# S2EC13.net
KiCad netlist of a schematic drawn in EAGLE
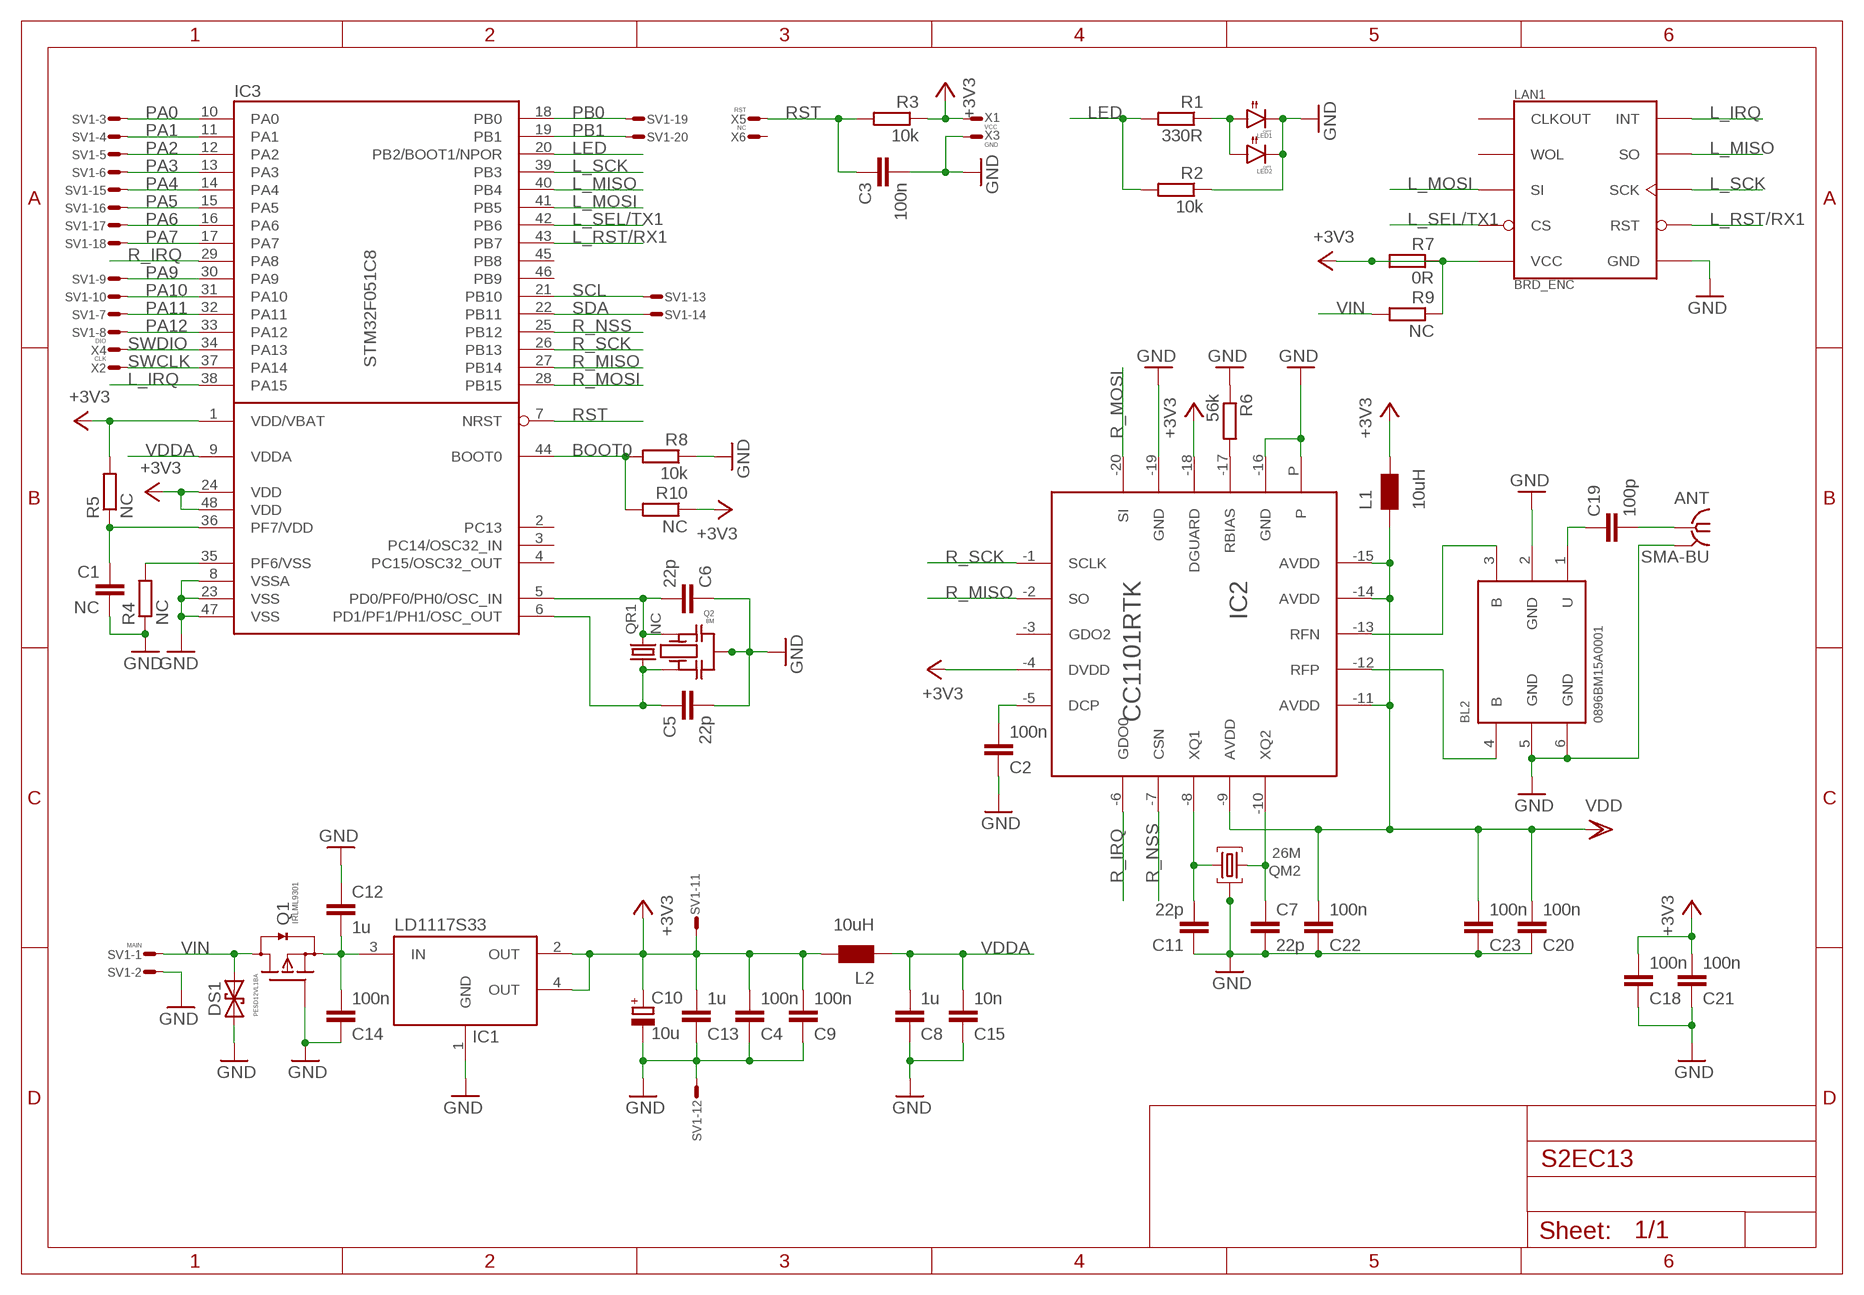
[diagram p0: schematic, sheet 1]

(export (version "E")
  (design (tool "Eeschema 10.0.6"))
  (components
    (comp (ref "ANT")
      (value "SMA-BU")
      (footprint "eagle-import:BU-SMA-V")
      (libsource (lib "eagle-import") (part "SMA-BU"))
    )
    (comp (ref "BL2")
      (value "0896BM15A0001")
      (footprint "eagle-import:BL")
      (libsource (lib "eagle-import") (part "BL"))
    )
    (comp (ref "C1")
      (value "NC")
      (footprint "eagle-import:0603")
      (libsource (lib "eagle-import") (part "C0603"))
    )
    (comp (ref "C2")
      (value "100n")
      (footprint "eagle-import:0603")
      (libsource (lib "eagle-import") (part "C0603"))
    )
    (comp (ref "C3")
      (value "100n")
      (footprint "eagle-import:0603")
      (libsource (lib "eagle-import") (part "C0603"))
    )
    (comp (ref "C4")
      (value "100n")
      (footprint "eagle-import:0603")
      (libsource (lib "eagle-import") (part "C0603"))
    )
    (comp (ref "C5")
      (value "22p")
      (footprint "eagle-import:0603")
      (libsource (lib "eagle-import") (part "C0603"))
    )
    (comp (ref "C6")
      (value "22p")
      (footprint "eagle-import:0603")
      (libsource (lib "eagle-import") (part "C0603"))
    )
    (comp (ref "C7")
      (value "22p")
      (footprint "eagle-import:0603")
      (libsource (lib "eagle-import") (part "C0603"))
    )
    (comp (ref "C8")
      (value "1u")
      (footprint "eagle-import:0603")
      (libsource (lib "eagle-import") (part "C0603"))
    )
    (comp (ref "C9")
      (value "100n")
      (footprint "eagle-import:0603")
      (libsource (lib "eagle-import") (part "C0603"))
    )
    (comp (ref "C10")
      (value "10u")
      (footprint "eagle-import:SMC_A")
      (libsource (lib "eagle-import") (part "C_POLSMCA"))
    )
    (comp (ref "C11")
      (value "22p")
      (footprint "eagle-import:0603")
      (libsource (lib "eagle-import") (part "C0603"))
    )
    (comp (ref "C12")
      (value "1u")
      (footprint "eagle-import:0603")
      (libsource (lib "eagle-import") (part "C0603"))
    )
    (comp (ref "C13")
      (value "1u")
      (footprint "eagle-import:0603")
      (libsource (lib "eagle-import") (part "C0603"))
    )
    (comp (ref "C14")
      (value "100n")
      (footprint "eagle-import:0603")
      (libsource (lib "eagle-import") (part "C0603"))
    )
    (comp (ref "C15")
      (value "10n")
      (footprint "eagle-import:0603")
      (libsource (lib "eagle-import") (part "C0603"))
    )
    (comp (ref "C18")
      (value "100n")
      (footprint "eagle-import:0603")
      (libsource (lib "eagle-import") (part "C0603"))
    )
    (comp (ref "C19")
      (value "100p")
      (footprint "eagle-import:0603")
      (libsource (lib "eagle-import") (part "C0603"))
    )
    (comp (ref "C20")
      (value "100n")
      (footprint "eagle-import:0603")
      (libsource (lib "eagle-import") (part "C0603"))
    )
    (comp (ref "C21")
      (value "100n")
      (footprint "eagle-import:0603")
      (libsource (lib "eagle-import") (part "C0603"))
    )
    (comp (ref "C22")
      (value "100n")
      (footprint "eagle-import:0603")
      (libsource (lib "eagle-import") (part "C0603"))
    )
    (comp (ref "C23")
      (value "100n")
      (footprint "eagle-import:0603")
      (libsource (lib "eagle-import") (part "C0603"))
    )
    (comp (ref "DS1")
      (value "PESD12VL1BA")
      (footprint "eagle-import:SOD323")
      (libsource (lib "eagle-import") (part "TVS-U323"))
    )
    (comp (ref "IC1")
      (value "LD1117S33")
      (footprint "eagle-import:SOT223")
      (libsource (lib "eagle-import") (part "LDO_4P"))
    )
    (comp (ref "IC2")
      (value "CC1101RTK")
      (footprint "eagle-import:VQFN20")
      (libsource (lib "eagle-import") (part "CC110LV"))
    )
    (comp (ref "IC3")
      (value "STM32F051C8")
      (footprint "eagle-import:LQFP48")
      (libsource (lib "eagle-import") (part "STM32_LQFP48"))
    )
    (comp (ref "L1")
      (value "10uH")
      (footprint "eagle-import:0603")
      (libsource (lib "eagle-import") (part "L0603"))
    )
    (comp (ref "L2")
      (value "10uH")
      (footprint "eagle-import:0603")
      (libsource (lib "eagle-import") (part "L0603"))
    )
    (comp (ref "LAN1")
      (value "BRD_ENC")
      (footprint "eagle-import:BRD_ENC")
      (libsource (lib "eagle-import") (part "BRD_ENC"))
    )
    (comp (ref "LED1")
      (value "OPT")
      (footprint "eagle-import:T1-3_4")
      (libsource (lib "eagle-import") (part "LEDT134"))
    )
    (comp (ref "LED2")
      (value "OPT")
      (footprint "eagle-import:1206")
      (libsource (lib "eagle-import") (part "LED1206"))
    )
    (comp (ref "Q1")
      (value "IRLML9301")
      (footprint "eagle-import:SOT23")
      (libsource (lib "eagle-import") (part "FET-PDSOT23"))
    )
    (comp (ref "Q2")
      (value "8M")
      (footprint "eagle-import:CSTCE")
      (libsource (lib "eagle-import") (part "QRCE"))
    )
    (comp (ref "QM2")
      (value "26M")
      (footprint "eagle-import:SMD_4P_3.2X2.5")
      (libsource (lib "eagle-import") (part "QM3.2X2.5"))
    )
    (comp (ref "QR1")
      (value "NC")
      (footprint "eagle-import:ABS07")
      (libsource (lib "eagle-import") (part "QABS07"))
    )
    (comp (ref "R1")
      (value "330R")
      (footprint "eagle-import:0603")
      (libsource (lib "eagle-import") (part "R0603"))
    )
    (comp (ref "R2")
      (value "10k")
      (footprint "eagle-import:0603")
      (libsource (lib "eagle-import") (part "R0603"))
    )
    (comp (ref "R3")
      (value "10k")
      (footprint "eagle-import:0603")
      (libsource (lib "eagle-import") (part "R0603"))
    )
    (comp (ref "R4")
      (value "NC")
      (footprint "eagle-import:0603")
      (libsource (lib "eagle-import") (part "R0603"))
    )
    (comp (ref "R5")
      (value "NC")
      (footprint "eagle-import:0603")
      (libsource (lib "eagle-import") (part "R0603"))
    )
    (comp (ref "R6")
      (value "56k")
      (footprint "eagle-import:0603")
      (libsource (lib "eagle-import") (part "R0603"))
    )
    (comp (ref "R7")
      (value "0R")
      (footprint "eagle-import:0603")
      (libsource (lib "eagle-import") (part "R0603"))
    )
    (comp (ref "R8")
      (value "10k")
      (footprint "eagle-import:0603")
      (libsource (lib "eagle-import") (part "R0603"))
    )
    (comp (ref "R9")
      (value "NC")
      (footprint "eagle-import:0603")
      (libsource (lib "eagle-import") (part "R0603"))
    )
    (comp (ref "R10")
      (value "NC")
      (footprint "eagle-import:0603")
      (libsource (lib "eagle-import") (part "R0603"))
    )
    (comp (ref "SV1")
      (value "MAIN")
      (footprint "eagle-import:ML20LS")
      (libsource (lib "eagle-import") (part "ML20?ELS"))
    )
    (comp (ref "X1")
      (value "VCC")
      (footprint "eagle-import:T1.6_0.9")
      (libsource (lib "eagle-import") (part "WIREPADT1.6/0.9"))
    )
    (comp (ref "X2")
      (value "CLK")
      (footprint "eagle-import:T1.6_0.9")
      (libsource (lib "eagle-import") (part "WIREPADT1.6/0.9"))
    )
    (comp (ref "X3")
      (value "GND")
      (footprint "eagle-import:T1.6_0.9")
      (libsource (lib "eagle-import") (part "WIREPADT1.6/0.9"))
    )
    (comp (ref "X4")
      (value "DIO")
      (footprint "eagle-import:T1.6_0.9")
      (libsource (lib "eagle-import") (part "WIREPADT1.6/0.9"))
    )
    (comp (ref "X5")
      (value "RST")
      (footprint "eagle-import:T1.6_0.9")
      (libsource (lib "eagle-import") (part "WIREPADT1.6/0.9"))
    )
    (comp (ref "X6")
      (value "NC")
      (footprint "eagle-import:T1.6_0.9")
      (libsource (lib "eagle-import") (part "WIREPADT1.6/0.9"))
    )
  )
  (nets
    (net (code "1") (name "+3V3") (class "Default")
      (node (ref "C10") (pin "+") (pinfunction "+_+") (pintype "passive"))
      (node (ref "C13") (pin "2") (pinfunction "2_2") (pintype "passive"))
      (node (ref "C18") (pin "2") (pinfunction "2_2") (pintype "passive"))
      (node (ref "C21") (pin "2") (pinfunction "2_2") (pintype "passive"))
      (node (ref "C4") (pin "2") (pinfunction "2_2") (pintype "passive"))
      (node (ref "C9") (pin "2") (pinfunction "2_2") (pintype "passive"))
      (node (ref "IC1") (pin "2") (pinfunction "OUT_2") (pintype "bidirectional"))
      (node (ref "IC1") (pin "4") (pinfunction "OUT_4") (pintype "bidirectional"))
      (node (ref "IC2") (pin "-18") (pinfunction "DGUARD_-18") (pintype "bidirectional"))
      (node (ref "IC2") (pin "-4") (pinfunction "DVDD_-4") (pintype "bidirectional"))
      (node (ref "IC3") (pin "1") (pinfunction "VDD/VBAT_1") (pintype "bidirectional"))
      (node (ref "IC3") (pin "24") (pinfunction "VDD_24") (pintype "bidirectional"))
      (node (ref "IC3") (pin "48") (pinfunction "VDD_48") (pintype "bidirectional"))
      (node (ref "L1") (pin "2") (pinfunction "2_2") (pintype "passive"))
      (node (ref "L2") (pin "2") (pinfunction "2_2") (pintype "passive"))
      (node (ref "LAN1") (pin "P$9") (pinfunction "VCC_P$9") (pintype "bidirectional"))
      (node (ref "R10") (pin "1") (pinfunction "1_1") (pintype "passive"))
      (node (ref "R3") (pin "1") (pinfunction "1_1") (pintype "passive"))
      (node (ref "R5") (pin "2") (pinfunction "2_2") (pintype "passive"))
      (node (ref "R7") (pin "1") (pinfunction "1_1") (pintype "passive"))
      (node (ref "R7") (pin "2") (pinfunction "2_2") (pintype "passive"))
      (node (ref "R9") (pin "1") (pinfunction "1_1") (pintype "passive"))
      (node (ref "SV1") (pin "P$11") (pinfunction "S_P$11") (pintype "passive"))
      (node (ref "X1") (pin "1") (pinfunction "S_1") (pintype "passive"))
    )
    (net (code "2") (name "/BOOT0") (class "Default")
      (node (ref "IC3") (pin "44") (pinfunction "BOOT0_44") (pintype "bidirectional"))
      (node (ref "R10") (pin "2") (pinfunction "2_2") (pintype "passive"))
      (node (ref "R8") (pin "2") (pinfunction "2_2") (pintype "passive"))
    )
    (net (code "3") (name "/LED") (class "Default")
      (node (ref "IC3") (pin "20") (pinfunction "PB2/BOOT1/NPOR_20") (pintype "bidirectional"))
      (node (ref "R1") (pin "2") (pinfunction "2_2") (pintype "passive"))
      (node (ref "R2") (pin "2") (pinfunction "2_2") (pintype "passive"))
    )
    (net (code "4") (name "/L_IRQ") (class "Default")
      (node (ref "IC3") (pin "38") (pinfunction "PA15_38") (pintype "bidirectional"))
      (node (ref "LAN1") (pin "P$2") (pinfunction "INT_P$2") (pintype "open_collector"))
    )
    (net (code "5") (name "/L_MISO") (class "Default")
      (node (ref "IC3") (pin "40") (pinfunction "PB4_40") (pintype "bidirectional"))
      (node (ref "LAN1") (pin "P$4") (pinfunction "SO_P$4") (pintype "output"))
    )
    (net (code "6") (name "/L_MOSI") (class "Default")
      (node (ref "IC3") (pin "41") (pinfunction "PB5_41") (pintype "bidirectional"))
      (node (ref "LAN1") (pin "P$5") (pinfunction "SI_P$5") (pintype "input"))
    )
    (net (code "7") (name "/L_RST{slash}RX1") (class "Default")
      (node (ref "IC3") (pin "43") (pinfunction "PB7_43") (pintype "bidirectional"))
      (node (ref "LAN1") (pin "P$8") (pinfunction "RST_P$8") (pintype "bidirectional"))
    )
    (net (code "8") (name "/L_SCK") (class "Default")
      (node (ref "IC3") (pin "39") (pinfunction "PB3_39") (pintype "bidirectional"))
      (node (ref "LAN1") (pin "P$6") (pinfunction "SCK_P$6") (pintype "input"))
    )
    (net (code "9") (name "/L_SEL{slash}TX1") (class "Default")
      (node (ref "IC3") (pin "42") (pinfunction "PB6_42") (pintype "bidirectional"))
      (node (ref "LAN1") (pin "P$7") (pinfunction "CS_P$7") (pintype "input"))
    )
    (net (code "10") (name "/PA0") (class "Default")
      (node (ref "IC3") (pin "10") (pinfunction "PA0_10") (pintype "bidirectional"))
      (node (ref "SV1") (pin "P$3") (pinfunction "S_P$3") (pintype "passive"))
    )
    (net (code "11") (name "/PA1") (class "Default")
      (node (ref "IC3") (pin "11") (pinfunction "PA1_11") (pintype "bidirectional"))
      (node (ref "SV1") (pin "P$4") (pinfunction "S_P$4") (pintype "passive"))
    )
    (net (code "12") (name "/PA2") (class "Default")
      (node (ref "IC3") (pin "12") (pinfunction "PA2_12") (pintype "bidirectional"))
      (node (ref "SV1") (pin "P$5") (pinfunction "S_P$5") (pintype "passive"))
    )
    (net (code "13") (name "/PA3") (class "Default")
      (node (ref "IC3") (pin "13") (pinfunction "PA3_13") (pintype "bidirectional"))
      (node (ref "SV1") (pin "P$6") (pinfunction "S_P$6") (pintype "passive"))
    )
    (net (code "14") (name "/PA4") (class "Default")
      (node (ref "IC3") (pin "14") (pinfunction "PA4_14") (pintype "bidirectional"))
      (node (ref "SV1") (pin "P$15") (pinfunction "S_P$15") (pintype "passive"))
    )
    (net (code "15") (name "/PA5") (class "Default")
      (node (ref "IC3") (pin "15") (pinfunction "PA5_15") (pintype "bidirectional"))
      (node (ref "SV1") (pin "P$16") (pinfunction "S_P$16") (pintype "passive"))
    )
    (net (code "16") (name "/PA6") (class "Default")
      (node (ref "IC3") (pin "16") (pinfunction "PA6_16") (pintype "bidirectional"))
      (node (ref "SV1") (pin "P$17") (pinfunction "S_P$17") (pintype "passive"))
    )
    (net (code "17") (name "/PA7") (class "Default")
      (node (ref "IC3") (pin "17") (pinfunction "PA7_17") (pintype "bidirectional"))
      (node (ref "SV1") (pin "P$18") (pinfunction "S_P$18") (pintype "passive"))
    )
    (net (code "18") (name "/PA9") (class "Default")
      (node (ref "IC3") (pin "30") (pinfunction "PA9_30") (pintype "bidirectional"))
      (node (ref "SV1") (pin "P$9") (pinfunction "S_P$9") (pintype "passive"))
    )
    (net (code "19") (name "/PA10") (class "Default")
      (node (ref "IC3") (pin "31") (pinfunction "PA10_31") (pintype "bidirectional"))
      (node (ref "SV1") (pin "P$10") (pinfunction "S_P$10") (pintype "passive"))
    )
    (net (code "20") (name "/PA11") (class "Default")
      (node (ref "IC3") (pin "32") (pinfunction "PA11_32") (pintype "bidirectional"))
      (node (ref "SV1") (pin "P$7") (pinfunction "S_P$7") (pintype "passive"))
    )
    (net (code "21") (name "/PA12") (class "Default")
      (node (ref "IC3") (pin "33") (pinfunction "PA12_33") (pintype "bidirectional"))
      (node (ref "SV1") (pin "P$8") (pinfunction "S_P$8") (pintype "passive"))
    )
    (net (code "22") (name "/PB0") (class "Default")
      (node (ref "IC3") (pin "18") (pinfunction "PB0_18") (pintype "bidirectional"))
      (node (ref "SV1") (pin "P$19") (pinfunction "S_P$19") (pintype "passive"))
    )
    (net (code "23") (name "/PB1") (class "Default")
      (node (ref "IC3") (pin "19") (pinfunction "PB1_19") (pintype "bidirectional"))
      (node (ref "SV1") (pin "P$20") (pinfunction "S_P$20") (pintype "passive"))
    )
    (net (code "24") (name "/RST") (class "Default")
      (node (ref "C3") (pin "1") (pinfunction "1_1") (pintype "passive"))
      (node (ref "IC3") (pin "7") (pinfunction "NRST_7") (pintype "bidirectional"))
      (node (ref "R3") (pin "2") (pinfunction "2_2") (pintype "passive"))
      (node (ref "X5") (pin "1") (pinfunction "S_1") (pintype "passive"))
    )
    (net (code "25") (name "/R_IRQ") (class "Default")
      (node (ref "IC2") (pin "-6") (pinfunction "GDO0_-6") (pintype "bidirectional"))
      (node (ref "IC3") (pin "29") (pinfunction "PA8_29") (pintype "bidirectional"))
    )
    (net (code "26") (name "/R_MISO") (class "Default")
      (node (ref "IC2") (pin "-2") (pinfunction "SO_-2") (pintype "output"))
      (node (ref "IC3") (pin "27") (pinfunction "PB14_27") (pintype "bidirectional"))
    )
    (net (code "27") (name "/R_MOSI") (class "Default")
      (node (ref "IC2") (pin "-20") (pinfunction "SI_-20") (pintype "input"))
      (node (ref "IC3") (pin "28") (pinfunction "PB15_28") (pintype "bidirectional"))
    )
    (net (code "28") (name "/R_NSS") (class "Default")
      (node (ref "IC2") (pin "-7") (pinfunction "CSN_-7") (pintype "input"))
      (node (ref "IC3") (pin "25") (pinfunction "PB12_25") (pintype "bidirectional"))
    )
    (net (code "29") (name "/R_SCK") (class "Default")
      (node (ref "IC2") (pin "-1") (pinfunction "SCLK_-1") (pintype "input"))
      (node (ref "IC3") (pin "26") (pinfunction "PB13_26") (pintype "bidirectional"))
    )
    (net (code "30") (name "/SCL") (class "Default")
      (node (ref "IC3") (pin "21") (pinfunction "PB10_21") (pintype "bidirectional"))
      (node (ref "SV1") (pin "P$13") (pinfunction "S_P$13") (pintype "passive"))
    )
    (net (code "31") (name "/SDA") (class "Default")
      (node (ref "IC3") (pin "22") (pinfunction "PB11_22") (pintype "bidirectional"))
      (node (ref "SV1") (pin "P$14") (pinfunction "S_P$14") (pintype "passive"))
    )
    (net (code "32") (name "/SWCLK") (class "Default")
      (node (ref "IC3") (pin "37") (pinfunction "PA14_37") (pintype "bidirectional"))
      (node (ref "X2") (pin "1") (pinfunction "S_1") (pintype "passive"))
    )
    (net (code "33") (name "/SWDIO") (class "Default")
      (node (ref "IC3") (pin "34") (pinfunction "PA13_34") (pintype "bidirectional"))
      (node (ref "X4") (pin "1") (pinfunction "S_1") (pintype "passive"))
    )
    (net (code "34") (name "/VDDA") (class "Default")
      (node (ref "C15") (pin "2") (pinfunction "2_2") (pintype "passive"))
      (node (ref "C8") (pin "2") (pinfunction "2_2") (pintype "passive"))
      (node (ref "IC3") (pin "9") (pinfunction "VDDA_9") (pintype "bidirectional"))
      (node (ref "L2") (pin "1") (pinfunction "1_1") (pintype "passive"))
    )
    (net (code "35") (name "/VIN") (class "Default")
      (node (ref "DS1") (pin "C") (pinfunction "2_C") (pintype "passive"))
      (node (ref "Q1") (pin "3") (pinfunction "D_3") (pintype "passive"))
      (node (ref "R9") (pin "2") (pinfunction "2_2") (pintype "passive"))
      (node (ref "SV1") (pin "P$1") (pinfunction "S_P$1") (pintype "passive"))
    )
    (net (code "36") (name "GND") (class "Default")
      (node (ref "ANT") (pin "2") (pinfunction "2_2") (pintype "passive"))
      (node (ref "ANT") (pin "3") (pinfunction "2_3") (pintype "passive"))
      (node (ref "ANT") (pin "4") (pinfunction "2_4") (pintype "passive"))
      (node (ref "ANT") (pin "5") (pinfunction "2_5") (pintype "passive"))
      (node (ref "BL2") (pin "2") (pinfunction "GND_2") (pintype "bidirectional"))
      (node (ref "BL2") (pin "5") (pinfunction "GND_5") (pintype "bidirectional"))
      (node (ref "BL2") (pin "6") (pinfunction "GND_6") (pintype "bidirectional"))
      (node (ref "C1") (pin "2") (pinfunction "2_2") (pintype "passive"))
      (node (ref "C10") (pin "-") (pinfunction "-_-") (pintype "passive"))
      (node (ref "C11") (pin "1") (pinfunction "1_1") (pintype "passive"))
      (node (ref "C12") (pin "1") (pinfunction "1_1") (pintype "passive"))
      (node (ref "C13") (pin "1") (pinfunction "1_1") (pintype "passive"))
      (node (ref "C14") (pin "1") (pinfunction "1_1") (pintype "passive"))
      (node (ref "C15") (pin "1") (pinfunction "1_1") (pintype "passive"))
      (node (ref "C18") (pin "1") (pinfunction "1_1") (pintype "passive"))
      (node (ref "C2") (pin "1") (pinfunction "1_1") (pintype "passive"))
      (node (ref "C20") (pin "1") (pinfunction "1_1") (pintype "passive"))
      (node (ref "C21") (pin "1") (pinfunction "1_1") (pintype "passive"))
      (node (ref "C22") (pin "1") (pinfunction "1_1") (pintype "passive"))
      (node (ref "C23") (pin "1") (pinfunction "1_1") (pintype "passive"))
      (node (ref "C3") (pin "2") (pinfunction "2_2") (pintype "passive"))
      (node (ref "C4") (pin "1") (pinfunction "1_1") (pintype "passive"))
      (node (ref "C5") (pin "2") (pinfunction "2_2") (pintype "passive"))
      (node (ref "C6") (pin "1") (pinfunction "1_1") (pintype "passive"))
      (node (ref "C7") (pin "2") (pinfunction "2_2") (pintype "passive"))
      (node (ref "C8") (pin "1") (pinfunction "1_1") (pintype "passive"))
      (node (ref "C9") (pin "1") (pinfunction "1_1") (pintype "passive"))
      (node (ref "DS1") (pin "A") (pinfunction "1_A") (pintype "passive"))
      (node (ref "IC1") (pin "1") (pinfunction "GND_1") (pintype "bidirectional"))
      (node (ref "IC2") (pin "-16") (pinfunction "GND_-16") (pintype "bidirectional"))
      (node (ref "IC2") (pin "-19") (pinfunction "GND_-19") (pintype "bidirectional"))
      (node (ref "IC2") (pin "P") (pinfunction "P_P") (pintype "bidirectional"))
      (node (ref "IC3") (pin "23") (pinfunction "VSS_23") (pintype "bidirectional"))
      (node (ref "IC3") (pin "47") (pinfunction "VSS_47") (pintype "bidirectional"))
      (node (ref "IC3") (pin "8") (pinfunction "VSSA_8") (pintype "bidirectional"))
      (node (ref "LAN1") (pin "P$10") (pinfunction "GND_P$10") (pintype "bidirectional"))
      (node (ref "LED1") (pin "C") (pinfunction "C_C") (pintype "bidirectional"))
      (node (ref "LED2") (pin "2") (pinfunction "C_2") (pintype "bidirectional"))
      (node (ref "Q1") (pin "1") (pinfunction "G_1") (pintype "passive"))
      (node (ref "Q2") (pin "G") (pinfunction "M_G") (pintype "passive"))
      (node (ref "QM2") (pin "2") (pinfunction "M1_2") (pintype "passive"))
      (node (ref "QM2") (pin "4") (pinfunction "M2_4") (pintype "passive"))
      (node (ref "R2") (pin "1") (pinfunction "1_1") (pintype "passive"))
      (node (ref "R4") (pin "1") (pinfunction "1_1") (pintype "passive"))
      (node (ref "R6") (pin "1") (pinfunction "1_1") (pintype "passive"))
      (node (ref "R8") (pin "1") (pinfunction "1_1") (pintype "passive"))
      (node (ref "SV1") (pin "P$12") (pinfunction "S_P$12") (pintype "passive"))
      (node (ref "SV1") (pin "P$2") (pinfunction "S_P$2") (pintype "passive"))
      (node (ref "X3") (pin "1") (pinfunction "S_1") (pintype "passive"))
    )
    (net (code "37") (name "Net-(ANT-Pad1)") (class "Default")
      (node (ref "ANT") (pin "1") (pinfunction "1_1") (pintype "passive"))
      (node (ref "C19") (pin "2") (pinfunction "2_2") (pintype "passive"))
    )
    (net (code "38") (name "Net-(BL2-U)") (class "Default")
      (node (ref "BL2") (pin "1") (pinfunction "U_1") (pintype "bidirectional"))
      (node (ref "C19") (pin "1") (pinfunction "1_1") (pintype "passive"))
    )
    (net (code "39") (name "Net-(IC1-IN)") (class "Default")
      (node (ref "C12") (pin "2") (pinfunction "2_2") (pintype "passive"))
      (node (ref "C14") (pin "2") (pinfunction "2_2") (pintype "passive"))
      (node (ref "IC1") (pin "3") (pinfunction "IN_3") (pintype "bidirectional"))
      (node (ref "Q1") (pin "2") (pinfunction "S_2") (pintype "passive"))
    )
    (net (code "40") (name "Net-(IC2-DCP)") (class "Default")
      (node (ref "C2") (pin "2") (pinfunction "2_2") (pintype "passive"))
      (node (ref "IC2") (pin "-5") (pinfunction "DCP_-5") (pintype "bidirectional"))
    )
    (net (code "41") (name "Net-(IC2-RBIAS)") (class "Default")
      (node (ref "IC2") (pin "-17") (pinfunction "RBIAS_-17") (pintype "bidirectional"))
      (node (ref "R6") (pin "2") (pinfunction "2_2") (pintype "passive"))
    )
    (net (code "42") (name "Net-(IC2-RFN)") (class "Default")
      (node (ref "BL2") (pin "3") (pinfunction "B_3") (pintype "bidirectional"))
      (node (ref "IC2") (pin "-13") (pinfunction "RFN_-13") (pintype "bidirectional"))
    )
    (net (code "43") (name "Net-(IC2-RFP)") (class "Default")
      (node (ref "BL2") (pin "4") (pinfunction "B_4") (pintype "bidirectional"))
      (node (ref "IC2") (pin "-12") (pinfunction "RFP_-12") (pintype "bidirectional"))
    )
    (net (code "44") (name "Net-(IC2-XQ1)") (class "Default")
      (node (ref "C11") (pin "2") (pinfunction "2_2") (pintype "passive"))
      (node (ref "IC2") (pin "-8") (pinfunction "XQ1_-8") (pintype "bidirectional"))
      (node (ref "QM2") (pin "3") (pinfunction "2_3") (pintype "passive"))
    )
    (net (code "45") (name "Net-(IC2-XQ2)") (class "Default")
      (node (ref "C7") (pin "1") (pinfunction "1_1") (pintype "passive"))
      (node (ref "IC2") (pin "-10") (pinfunction "XQ2_-10") (pintype "bidirectional"))
      (node (ref "QM2") (pin "1") (pinfunction "1_1") (pintype "passive"))
    )
    (net (code "46") (name "Net-(IC3-PD0{slash}PF0{slash}PH0{slash}OSC_IN)") (class "Default")
      (node (ref "C6") (pin "2") (pinfunction "2_2") (pintype "passive"))
      (node (ref "IC3") (pin "5") (pinfunction "PD0/PF0/PH0/OSC_IN_5") (pintype "bidirectional"))
      (node (ref "Q2") (pin "A") (pinfunction "1_A") (pintype "passive"))
      (node (ref "QR1") (pin "P$2") (pinfunction "2_P$2") (pintype "passive"))
    )
    (net (code "47") (name "Net-(IC3-PD1{slash}PF1{slash}PH1{slash}OSC_OUT)") (class "Default")
      (node (ref "C5") (pin "1") (pinfunction "1_1") (pintype "passive"))
      (node (ref "IC3") (pin "6") (pinfunction "PD1/PF1/PH1/OSC_OUT_6") (pintype "bidirectional"))
      (node (ref "Q2") (pin "B") (pinfunction "2_B") (pintype "passive"))
      (node (ref "QR1") (pin "P$1") (pinfunction "1_P$1") (pintype "passive"))
    )
    (net (code "48") (name "Net-(IC3-PF6{slash}VSS)") (class "Default")
      (node (ref "IC3") (pin "35") (pinfunction "PF6/VSS_35") (pintype "bidirectional"))
      (node (ref "R4") (pin "2") (pinfunction "2_2") (pintype "passive"))
    )
    (net (code "49") (name "Net-(IC3-PF7{slash}VDD)") (class "Default")
      (node (ref "C1") (pin "1") (pinfunction "1_1") (pintype "passive"))
      (node (ref "IC3") (pin "36") (pinfunction "PF7/VDD_36") (pintype "bidirectional"))
      (node (ref "R5") (pin "1") (pinfunction "1_1") (pintype "passive"))
    )
    (net (code "50") (name "Net-(LED2-A)") (class "Default")
      (node (ref "LED1") (pin "A") (pinfunction "A_A") (pintype "bidirectional"))
      (node (ref "LED2") (pin "1") (pinfunction "A_1") (pintype "bidirectional"))
      (node (ref "R1") (pin "1") (pinfunction "1_1") (pintype "passive"))
    )
    (net (code "51") (name "VDD") (class "Default")
      (node (ref "C20") (pin "2") (pinfunction "2_2") (pintype "passive"))
      (node (ref "C22") (pin "2") (pinfunction "2_2") (pintype "passive"))
      (node (ref "C23") (pin "2") (pinfunction "2_2") (pintype "passive"))
      (node (ref "IC2") (pin "-11") (pinfunction "AVDD_-11") (pintype "bidirectional"))
      (node (ref "IC2") (pin "-14") (pinfunction "AVDD_-14") (pintype "bidirectional"))
      (node (ref "IC2") (pin "-15") (pinfunction "AVDD_-15") (pintype "bidirectional"))
      (node (ref "IC2") (pin "-9") (pinfunction "AVDD_-9") (pintype "bidirectional"))
      (node (ref "L1") (pin "1") (pinfunction "1_1") (pintype "passive"))
    )
    (net (code "52") (name "unconnected-(IC2-GDO2-Pad-3)") (class "Default")
      (node (ref "IC2") (pin "-3") (pinfunction "GDO2_-3") (pintype "output"))
    )
    (net (code "53") (name "unconnected-(IC3-PB8-Pad45)") (class "Default")
      (node (ref "IC3") (pin "45") (pinfunction "PB8_45") (pintype "bidirectional"))
    )
    (net (code "54") (name "unconnected-(IC3-PB9-Pad46)") (class "Default")
      (node (ref "IC3") (pin "46") (pinfunction "PB9_46") (pintype "bidirectional"))
    )
    (net (code "55") (name "unconnected-(IC3-PC13-Pad2)") (class "Default")
      (node (ref "IC3") (pin "2") (pinfunction "PC13_2") (pintype "bidirectional"))
    )
    (net (code "56") (name "unconnected-(IC3-PC14{slash}OSC32_IN-Pad3)") (class "Default")
      (node (ref "IC3") (pin "3") (pinfunction "PC14/OSC32_IN_3") (pintype "bidirectional"))
    )
    (net (code "57") (name "unconnected-(IC3-PC15{slash}OSC32_OUT-Pad4)") (class "Default")
      (node (ref "IC3") (pin "4") (pinfunction "PC15/OSC32_OUT_4") (pintype "bidirectional"))
    )
    (net (code "58") (name "unconnected-(LAN1-CLKOUT-PadP$1)") (class "Default")
      (node (ref "LAN1") (pin "P$1") (pinfunction "CLKOUT_P$1") (pintype "output"))
    )
    (net (code "59") (name "unconnected-(LAN1-WOL-PadP$3)") (class "Default")
      (node (ref "LAN1") (pin "P$3") (pinfunction "WOL_P$3") (pintype "output"))
    )
    (net (code "60") (name "unconnected-(X6-S-Pad1)") (class "Default")
      (node (ref "X6") (pin "1") (pinfunction "S_1") (pintype "passive"))
    )
  )
)
